# RF-Test-2.net
KiCad netlist of a schematic drawn in EAGLE
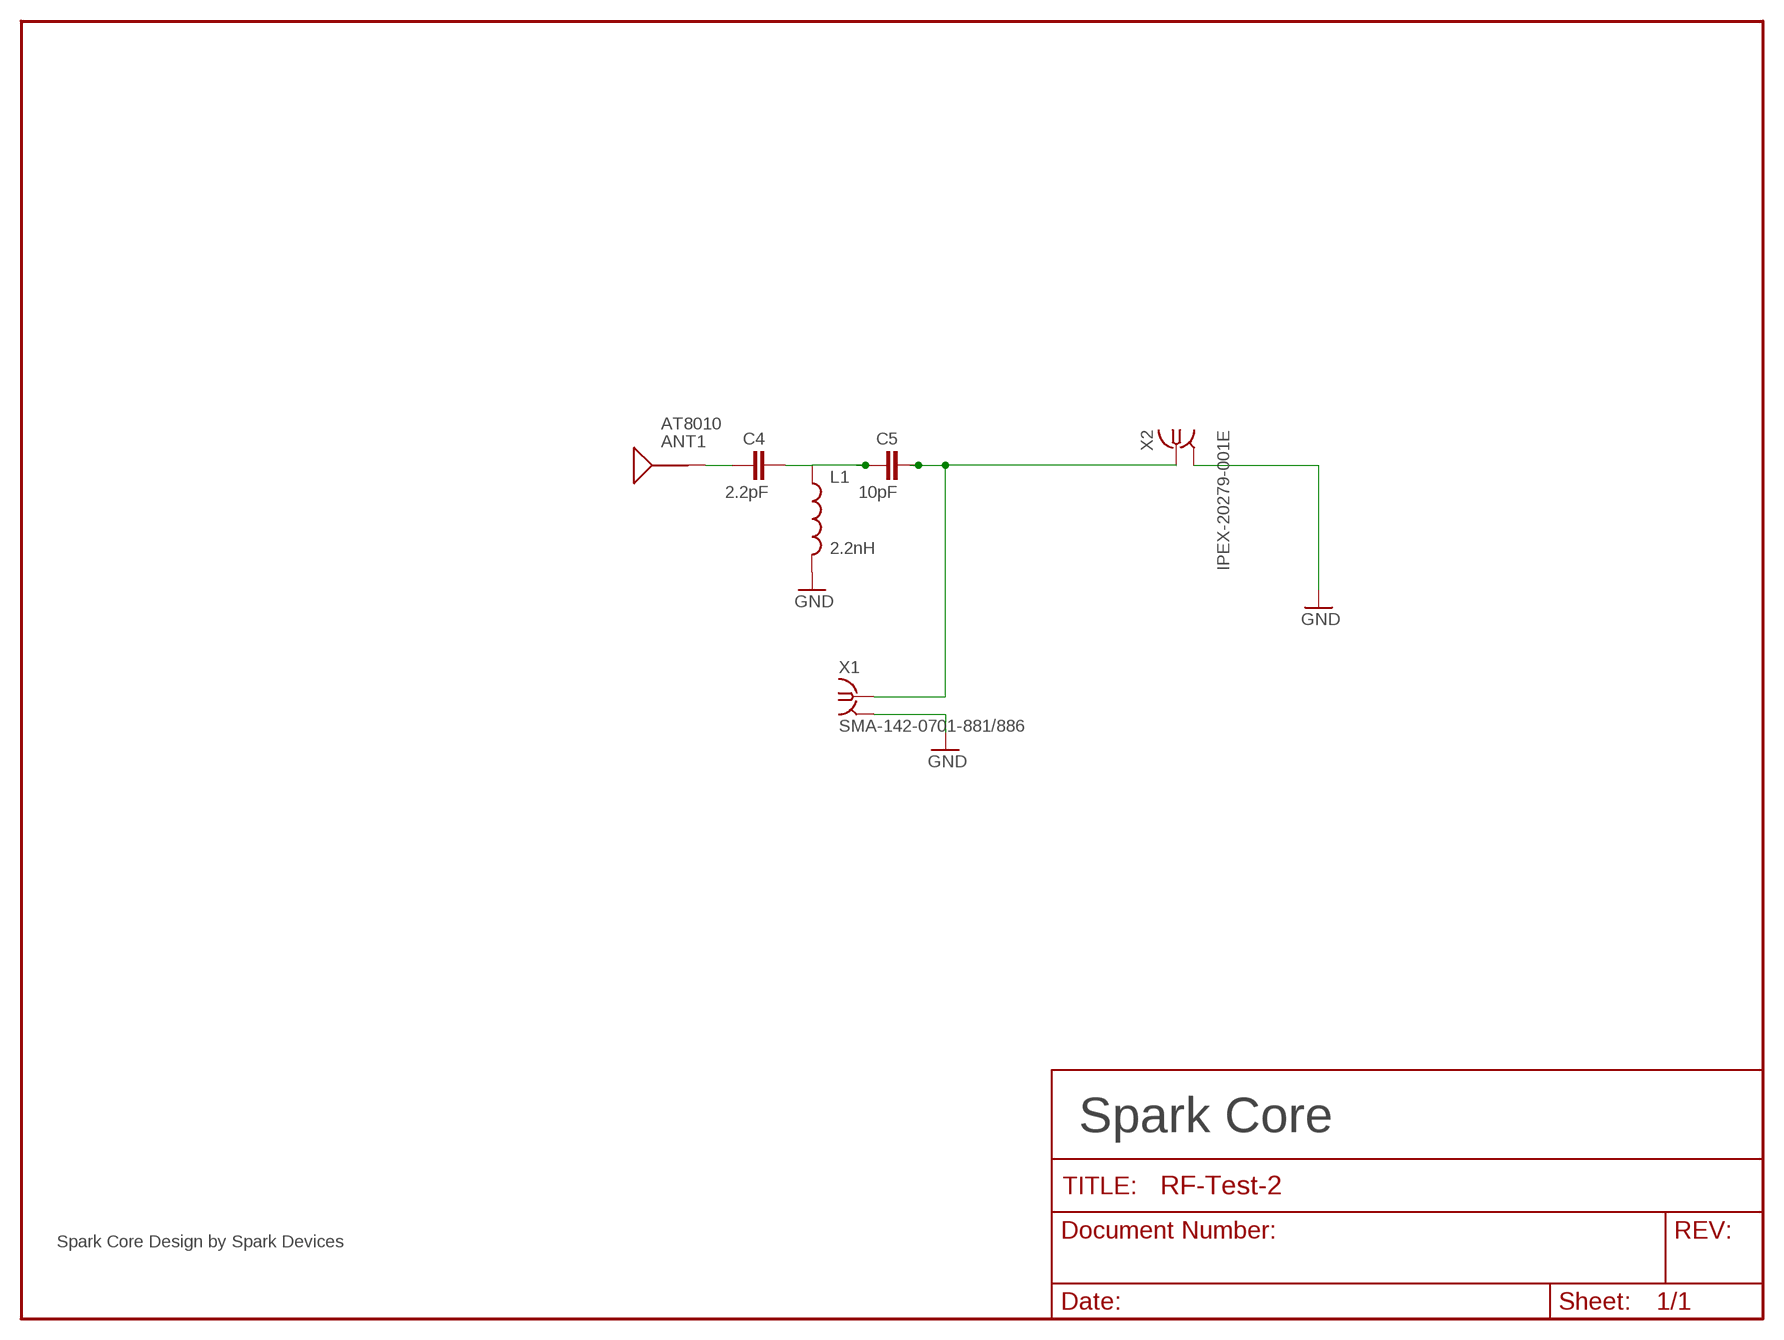
[diagram p0: schematic, sheet 1]

(export (version "E")
  (design (tool "Eeschema 10.0.6"))
  (components
    (comp (ref "ANT1")
      (value "AT8010")
      (footprint "eagle-import:AT8010")
      (libsource (lib "eagle-import") (part "AT8010"))
    )
    (comp (ref "C4")
      (value "2.2pF")
      (footprint "eagle-import:C0603")
      (libsource (lib "eagle-import") (part "C-EUC0603"))
    )
    (comp (ref "C5")
      (value "10pF")
      (footprint "eagle-import:C0603")
      (libsource (lib "eagle-import") (part "C-EUC0603"))
    )
    (comp (ref "L1")
      (value "2.2nH")
      (footprint "eagle-import:0603")
      (libsource (lib "eagle-import") (part "INDUCTOR0603"))
    )
    (comp (ref "X1")
      (value "SMA-142-0701-881/886")
      (footprint "eagle-import:ANDYW-GENERIC-END-LAUNCH")
      (fields (field (name "MF") "JOHNSON COMPONENTS") (field (name "MPN") "142-0701-881"))
      (libsource (lib "eagle-import") (part "SMA-142-0701-881/886"))
    )
    (comp (ref "X2")
      (value "IPEX-20279-001E")
      (footprint "eagle-import:IPEX-20279-001E")
      (libsource (lib "eagle-import") (part "IPEX-20279-001E"))
    )
  )
  (nets
    (net (code "1") (name "GND") (class "Default")
      (node (ref "L1") (pin "2") (pinfunction "2_2") (pintype "passive"))
      (node (ref "X1") (pin "G@1") (pinfunction "2_G@1") (pintype "passive"))
      (node (ref "X1") (pin "G@2") (pinfunction "2_G@2") (pintype "passive"))
      (node (ref "X1") (pin "G@3") (pinfunction "2_G@3") (pintype "passive"))
      (node (ref "X1") (pin "G@4") (pinfunction "2_G@4") (pintype "passive"))
      (node (ref "X2") (pin "2@1") (pinfunction "GND_2@1") (pintype "passive"))
      (node (ref "X2") (pin "2@2") (pinfunction "GND_2@2") (pintype "passive"))
    )
    (net (code "2") (name "Net-(ANT1-SIGNAL)") (class "Default")
      (node (ref "ANT1") (pin "SIG") (pinfunction "SIGNAL_SIG") (pintype "bidirectional"))
      (node (ref "C4") (pin "1") (pinfunction "1_1") (pintype "passive"))
    )
    (net (code "3") (name "Net-(C4-Pad2)") (class "Default")
      (node (ref "C4") (pin "2") (pinfunction "2_2") (pintype "passive"))
      (node (ref "C5") (pin "1") (pinfunction "1_1") (pintype "passive"))
      (node (ref "L1") (pin "1") (pinfunction "1_1") (pintype "passive"))
    )
    (net (code "4") (name "Net-(C5-Pad2)") (class "Default")
      (node (ref "C5") (pin "2") (pinfunction "2_2") (pintype "passive"))
      (node (ref "X1") (pin "1") (pinfunction "1_1") (pintype "passive"))
      (node (ref "X2") (pin "1") (pinfunction "1_1") (pintype "passive"))
    )
  )
)
